# servo.net
KiCad netlist of a schematic drawn in EAGLE
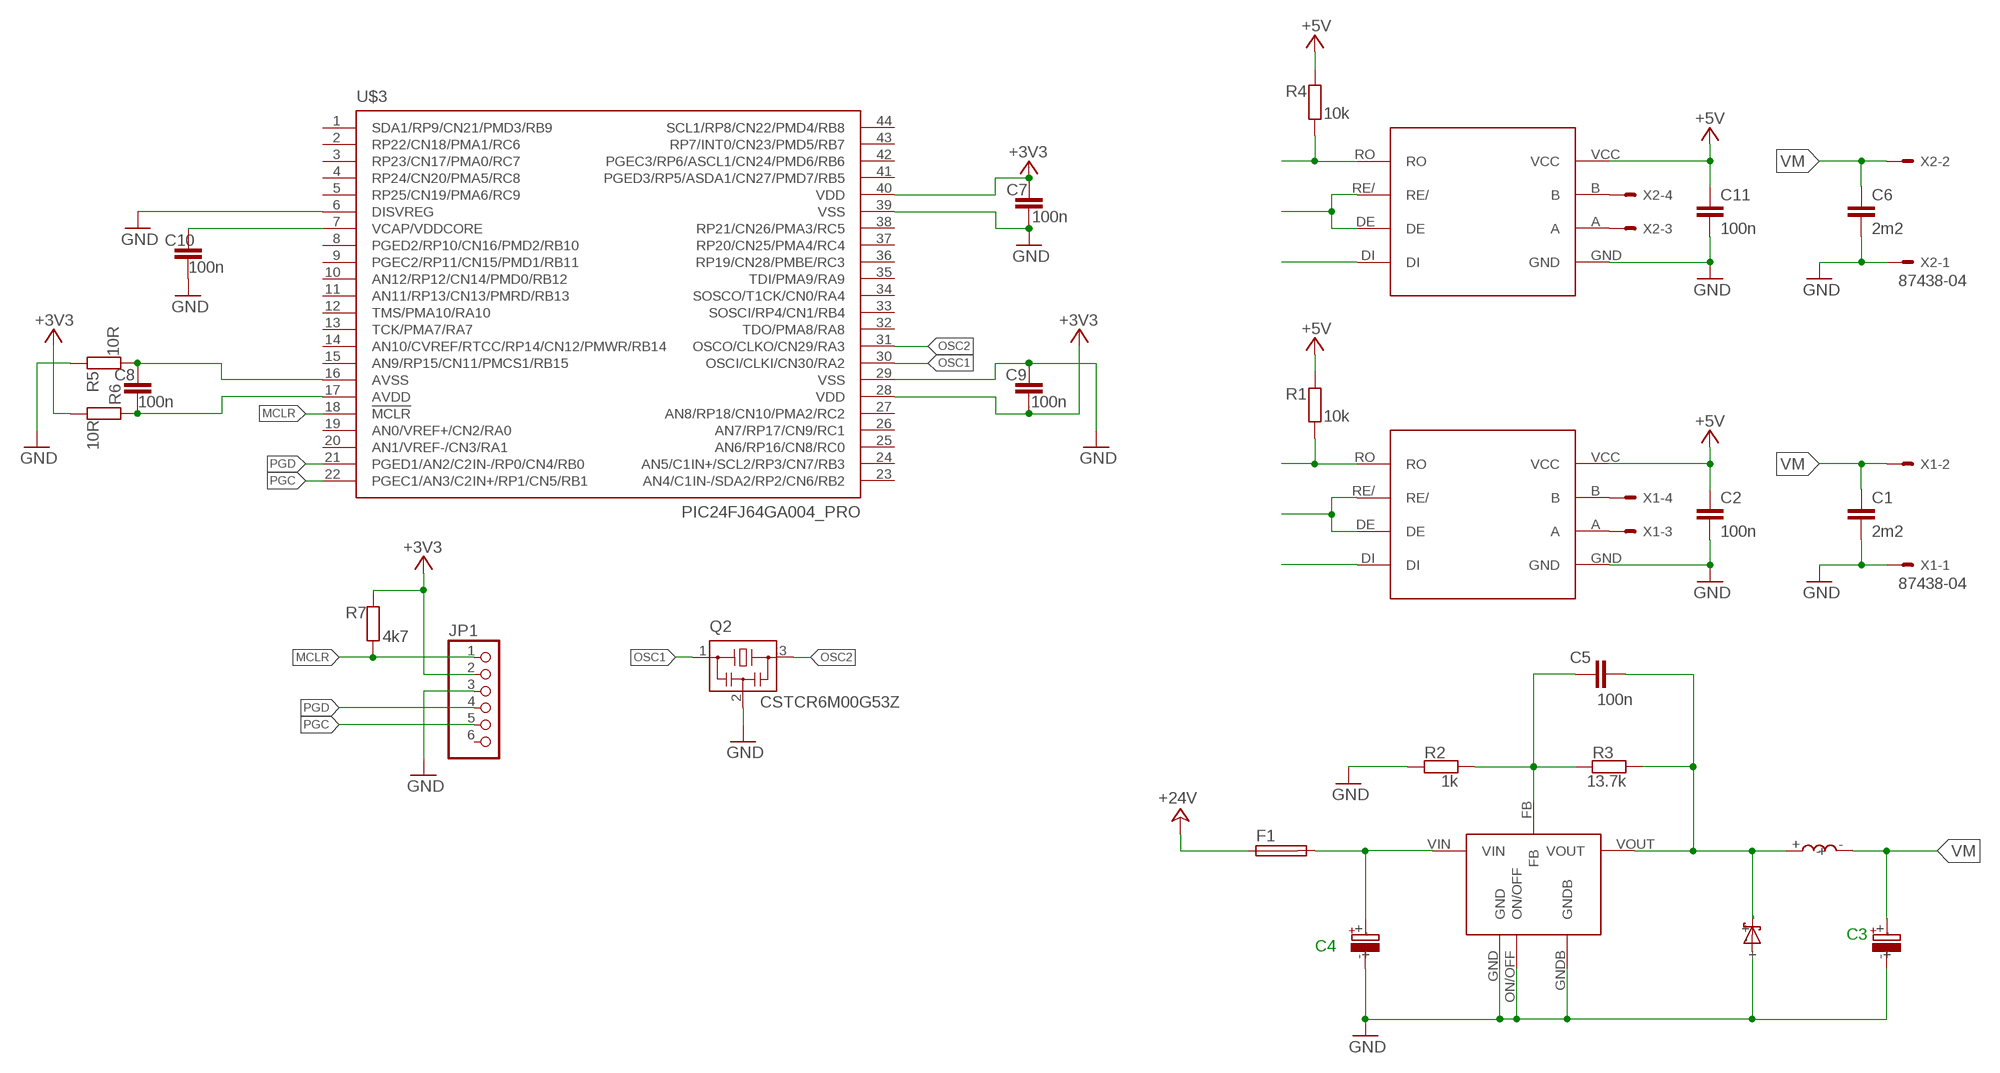
[diagram p0: schematic, sheet 1]

(export (version "E")
  (design (tool "Eeschema 10.0.6"))
  (components
    (comp (ref "C1")
      (value "2m2")
      (footprint "eagle-import:C1206")
      (libsource (lib "eagle-import") (part "resistor_C-EUC1206"))
    )
    (comp (ref "C2")
      (value "100n")
      (footprint "eagle-import:C1206")
      (libsource (lib "eagle-import") (part "resistor_C-EUC1206"))
    )
    (comp (ref "C3")
      (value "220uF")
      (footprint "eagle-import:C220")
      (libsource (lib "eagle-import") (part "C220"))
    )
    (comp (ref "C4")
      (value "680uF")
      (footprint "eagle-import:C680")
      (libsource (lib "eagle-import") (part "C680"))
    )
    (comp (ref "C5")
      (value "100n")
      (footprint "eagle-import:C1206")
      (libsource (lib "eagle-import") (part "resistor_C-EUC1206"))
    )
    (comp (ref "C6")
      (value "2m2")
      (footprint "eagle-import:C1206")
      (libsource (lib "eagle-import") (part "resistor_C-EUC1206"))
    )
    (comp (ref "C7")
      (value "100n")
      (footprint "eagle-import:C1206K")
      (libsource (lib "eagle-import") (part "C-EUC1206K"))
    )
    (comp (ref "C8")
      (value "100n")
      (footprint "eagle-import:C1206K")
      (libsource (lib "eagle-import") (part "C-EUC1206K"))
    )
    (comp (ref "C9")
      (value "100n")
      (footprint "eagle-import:C1206K")
      (libsource (lib "eagle-import") (part "C-EUC1206K"))
    )
    (comp (ref "C10")
      (value "100n")
      (footprint "eagle-import:C1206K")
      (libsource (lib "eagle-import") (part "C-EUC1206K"))
    )
    (comp (ref "C11")
      (value "100n")
      (footprint "eagle-import:C1206")
      (libsource (lib "eagle-import") (part "resistor_C-EUC1206"))
    )
    (comp (ref "F1")
      (value "SH22,5")
      (footprint "eagle-import:SH22,5")
      (fields (field (name "MF") "SCHURTER") (field (name "MPN") "0031.8201"))
      (libsource (lib "eagle-import") (part "SH22,5"))
    )
    (comp (ref "JP1")
      (value "PINHD-1X6")
      (footprint "eagle-import:1X06")
      (libsource (lib "eagle-import") (part "PINHD-1X6"))
    )
    (comp (ref "L1")
      (value "WE-PD")
      (footprint "eagle-import:WE-PD")
      (libsource (lib "eagle-import") (part "WE-PD"))
    )
    (comp (ref "N2")
      (value "MAX485")
      (footprint "eagle-import:SO08")
      (libsource (lib "eagle-import") (part "MAX485"))
    )
    (comp (ref "N3")
      (value "MAX485")
      (footprint "eagle-import:SO08")
      (libsource (lib "eagle-import") (part "MAX485"))
    )
    (comp (ref "Q2")
      (value "CSTCR6M00G53Z")
      (footprint "eagle-import:CSTER12M")
      (fields (field (name "MPN") "CSTCC12M0"))
      (libsource (lib "eagle-import") (part "CSTCR6M00G53Z"))
    )
    (comp (ref "R1")
      (value "10k")
      (footprint "eagle-import:R1206")
      (libsource (lib "eagle-import") (part "resistor_R-EU_R1206"))
    )
    (comp (ref "R2")
      (value "1k")
      (footprint "eagle-import:R1206")
      (libsource (lib "eagle-import") (part "resistor_R-EU_R1206"))
    )
    (comp (ref "R3")
      (value "13.7k")
      (footprint "eagle-import:R1206")
      (libsource (lib "eagle-import") (part "resistor_R-EU_R1206"))
    )
    (comp (ref "R4")
      (value "10k")
      (footprint "eagle-import:R1206")
      (libsource (lib "eagle-import") (part "resistor_R-EU_R1206"))
    )
    (comp (ref "R5")
      (value "10R")
      (footprint "eagle-import:M1206")
      (libsource (lib "eagle-import") (part "R-EU_M1206"))
    )
    (comp (ref "R6")
      (value "10R")
      (footprint "eagle-import:M1206")
      (libsource (lib "eagle-import") (part "R-EU_M1206"))
    )
    (comp (ref "R7")
      (value "4k7")
      (footprint "eagle-import:M1206")
      (libsource (lib "eagle-import") (part "R-EU_M1206"))
    )
    (comp (ref "U$1")
      (value "LM2596")
      (footprint "eagle-import:TO220")
      (libsource (lib "eagle-import") (part "LM2596"))
    )
    (comp (ref "U$2")
      (value "SCHOTTKY")
      (footprint "eagle-import:SCHOTTKY")
      (libsource (lib "eagle-import") (part "SCHOTTKY"))
    )
    (comp (ref "U$3")
      (value "PIC24FJ64GA004_PRO")
      (footprint "eagle-import:TQFP44")
      (libsource (lib "eagle-import") (part "PIC24FJ64GA004_PRO"))
    )
    (comp (ref "X1")
      (value "87438-04")
      (footprint "eagle-import:87438-04")
      (libsource (lib "eagle-import") (part "87438-04"))
    )
    (comp (ref "X2")
      (value "87438-04")
      (footprint "eagle-import:87438-04")
      (libsource (lib "eagle-import") (part "87438-04"))
    )
  )
  (nets
    (net (code "1") (name "+3V3") (class "Default")
      (node (ref "C7") (pin "2") (pinfunction "2_2") (pintype "passive"))
      (node (ref "C9") (pin "2") (pinfunction "2_2") (pintype "passive"))
      (node (ref "JP1") (pin "2") (pinfunction "2_2") (pintype "passive"))
      (node (ref "R6") (pin "2") (pinfunction "2_2") (pintype "passive"))
      (node (ref "R7") (pin "2") (pinfunction "2_2") (pintype "passive"))
      (node (ref "U$3") (pin "28") (pinfunction "VDD_28") (pintype "power_in"))
      (node (ref "U$3") (pin "40") (pinfunction "VDD_40") (pintype "power_in"))
    )
    (net (code "2") (name "+5V") (class "Default")
      (node (ref "C11") (pin "1") (pinfunction "1_1") (pintype "passive"))
      (node (ref "C2") (pin "1") (pinfunction "1_1") (pintype "passive"))
      (node (ref "N2") (pin "VCC") (pinfunction "VCC_VCC") (pintype "bidirectional"))
      (node (ref "N3") (pin "VCC") (pinfunction "VCC_VCC") (pintype "bidirectional"))
      (node (ref "R1") (pin "2") (pinfunction "2_2") (pintype "passive"))
      (node (ref "R4") (pin "2") (pinfunction "2_2") (pintype "passive"))
    )
    (net (code "3") (name "+24V") (class "Default")
      (node (ref "F1") (pin "1") (pinfunction "1_1") (pintype "passive"))
    )
    (net (code "4") (name "GND") (class "Default")
      (node (ref "C1") (pin "2") (pinfunction "2_2") (pintype "passive"))
      (node (ref "C10") (pin "2") (pinfunction "2_2") (pintype "passive"))
      (node (ref "C11") (pin "2") (pinfunction "2_2") (pintype "passive"))
      (node (ref "C2") (pin "2") (pinfunction "2_2") (pintype "passive"))
      (node (ref "C3") (pin "-") (pinfunction "-_-") (pintype "bidirectional"))
      (node (ref "C4") (pin "-") (pinfunction "-_-") (pintype "bidirectional"))
      (node (ref "C6") (pin "2") (pinfunction "2_2") (pintype "passive"))
      (node (ref "C7") (pin "1") (pinfunction "1_1") (pintype "passive"))
      (node (ref "C9") (pin "1") (pinfunction "1_1") (pintype "passive"))
      (node (ref "JP1") (pin "3") (pinfunction "3_3") (pintype "passive"))
      (node (ref "N2") (pin "GND") (pinfunction "GND_GND") (pintype "bidirectional"))
      (node (ref "N3") (pin "GND") (pinfunction "GND_GND") (pintype "bidirectional"))
      (node (ref "Q2") (pin "2") (pinfunction "2_2") (pintype "passive"))
      (node (ref "R2") (pin "2") (pinfunction "2_2") (pintype "passive"))
      (node (ref "R5") (pin "2") (pinfunction "2_2") (pintype "passive"))
      (node (ref "U$1") (pin "GND") (pinfunction "GND_GND") (pintype "bidirectional"))
      (node (ref "U$1") (pin "GNDB") (pinfunction "GNDB_GNDB") (pintype "bidirectional"))
      (node (ref "U$1") (pin "ON/OFF") (pinfunction "ON/OFF_ON/OFF") (pintype "bidirectional"))
      (node (ref "U$2") (pin "-") (pinfunction "-_-") (pintype "bidirectional"))
      (node (ref "U$3") (pin "29") (pinfunction "VSS_29") (pintype "power_in"))
      (node (ref "U$3") (pin "39") (pinfunction "VSS_39") (pintype "power_in"))
      (node (ref "U$3") (pin "6") (pinfunction "DISVREG_6") (pintype "passive"))
      (node (ref "X1") (pin "1") (pinfunction "S_1") (pintype "passive"))
      (node (ref "X2") (pin "1") (pinfunction "S_1") (pintype "passive"))
    )
    (net (code "5") (name "MCLR") (class "Default")
      (node (ref "JP1") (pin "1") (pinfunction "1_1") (pintype "passive"))
      (node (ref "R7") (pin "1") (pinfunction "1_1") (pintype "passive"))
      (node (ref "U$3") (pin "18") (pinfunction "~{MCLR}_18") (pintype "bidirectional"))
    )
    (net (code "6") (name "Net-(C4-Pad+)") (class "Default")
      (node (ref "C4") (pin "+") (pinfunction "+_+") (pintype "bidirectional"))
      (node (ref "F1") (pin "2") (pinfunction "2_2") (pintype "passive"))
      (node (ref "U$1") (pin "VIN") (pinfunction "VIN_VIN") (pintype "bidirectional"))
    )
    (net (code "7") (name "Net-(C5-Pad1)") (class "Default")
      (node (ref "C5") (pin "1") (pinfunction "1_1") (pintype "passive"))
      (node (ref "R2") (pin "1") (pinfunction "1_1") (pintype "passive"))
      (node (ref "R3") (pin "2") (pinfunction "2_2") (pintype "passive"))
      (node (ref "U$1") (pin "FB") (pinfunction "FB_FB") (pintype "bidirectional"))
    )
    (net (code "8") (name "Net-(C5-Pad2)") (class "Default")
      (node (ref "C5") (pin "2") (pinfunction "2_2") (pintype "passive"))
      (node (ref "L1") (pin "+") (pinfunction "+_+") (pintype "bidirectional"))
      (node (ref "R3") (pin "1") (pinfunction "1_1") (pintype "passive"))
      (node (ref "U$1") (pin "VOUT") (pinfunction "VOUT_VOUT") (pintype "bidirectional"))
      (node (ref "U$2") (pin "+") (pinfunction "+_+") (pintype "bidirectional"))
    )
    (net (code "9") (name "Net-(N2-PadDE)") (class "Default")
      (node (ref "N2") (pin "DE") (pinfunction "DE_DE") (pintype "bidirectional"))
      (node (ref "N2") (pin "RE/") (pinfunction "RE/_RE/") (pintype "bidirectional"))
    )
    (net (code "10") (name "Net-(N2-PadRO)") (class "Default")
      (node (ref "N2") (pin "RO") (pinfunction "RO_RO") (pintype "bidirectional"))
      (node (ref "R1") (pin "1") (pinfunction "1_1") (pintype "passive"))
    )
    (net (code "11") (name "Net-(N3-PadDE)") (class "Default")
      (node (ref "N3") (pin "DE") (pinfunction "DE_DE") (pintype "bidirectional"))
      (node (ref "N3") (pin "RE/") (pinfunction "RE/_RE/") (pintype "bidirectional"))
    )
    (net (code "12") (name "Net-(N3-PadRO)") (class "Default")
      (node (ref "N3") (pin "RO") (pinfunction "RO_RO") (pintype "bidirectional"))
      (node (ref "R4") (pin "1") (pinfunction "1_1") (pintype "passive"))
    )
    (net (code "13") (name "Net-(U$3-AVDD)") (class "Default")
      (node (ref "C8") (pin "2") (pinfunction "2_2") (pintype "passive"))
      (node (ref "R6") (pin "1") (pinfunction "1_1") (pintype "passive"))
      (node (ref "U$3") (pin "17") (pinfunction "AVDD_17") (pintype "power_in"))
    )
    (net (code "14") (name "Net-(U$3-AVSS)") (class "Default")
      (node (ref "C8") (pin "1") (pinfunction "1_1") (pintype "passive"))
      (node (ref "R5") (pin "1") (pinfunction "1_1") (pintype "passive"))
      (node (ref "U$3") (pin "16") (pinfunction "AVSS_16") (pintype "power_in"))
    )
    (net (code "15") (name "Net-(U$3-VCAP{slash}VDDCORE)") (class "Default")
      (node (ref "C10") (pin "1") (pinfunction "1_1") (pintype "passive"))
      (node (ref "U$3") (pin "7") (pinfunction "VCAP/VDDCORE_7") (pintype "power_in"))
    )
    (net (code "16") (name "Net-(X1C-S)") (class "Default")
      (node (ref "N2") (pin "A") (pinfunction "A_A") (pintype "bidirectional"))
      (node (ref "X1") (pin "3") (pinfunction "S_3") (pintype "passive"))
    )
    (net (code "17") (name "Net-(X1D-S)") (class "Default")
      (node (ref "N2") (pin "B") (pinfunction "B_B") (pintype "bidirectional"))
      (node (ref "X1") (pin "4") (pinfunction "S_4") (pintype "passive"))
    )
    (net (code "18") (name "Net-(X2C-S)") (class "Default")
      (node (ref "N3") (pin "A") (pinfunction "A_A") (pintype "bidirectional"))
      (node (ref "X2") (pin "3") (pinfunction "S_3") (pintype "passive"))
    )
    (net (code "19") (name "Net-(X2D-S)") (class "Default")
      (node (ref "N3") (pin "B") (pinfunction "B_B") (pintype "bidirectional"))
      (node (ref "X2") (pin "4") (pinfunction "S_4") (pintype "passive"))
    )
    (net (code "20") (name "OSC1") (class "Default")
      (node (ref "Q2") (pin "1") (pinfunction "1_1") (pintype "passive"))
      (node (ref "U$3") (pin "30") (pinfunction "OSCI/CLKI/CN30/RA2_30") (pintype "bidirectional"))
    )
    (net (code "21") (name "OSC2") (class "Default")
      (node (ref "Q2") (pin "3") (pinfunction "3_3") (pintype "passive"))
      (node (ref "U$3") (pin "31") (pinfunction "OSCO/CLKO/CN29/RA3_31") (pintype "bidirectional"))
    )
    (net (code "22") (name "PGC") (class "Default")
      (node (ref "JP1") (pin "5") (pinfunction "5_5") (pintype "passive"))
      (node (ref "U$3") (pin "22") (pinfunction "PGEC1/AN3/C2IN+/RP1/CN5/RB1_22") (pintype "bidirectional"))
    )
    (net (code "23") (name "PGD") (class "Default")
      (node (ref "JP1") (pin "4") (pinfunction "4_4") (pintype "passive"))
      (node (ref "U$3") (pin "21") (pinfunction "PGED1/AN2/C2IN-/RP0/CN4/RB0_21") (pintype "bidirectional"))
    )
    (net (code "24") (name "VM") (class "Default")
      (node (ref "C1") (pin "1") (pinfunction "1_1") (pintype "passive"))
      (node (ref "C3") (pin "+") (pinfunction "+_+") (pintype "bidirectional"))
      (node (ref "C6") (pin "1") (pinfunction "1_1") (pintype "passive"))
      (node (ref "L1") (pin "-") (pinfunction "-_-") (pintype "bidirectional"))
      (node (ref "X1") (pin "2") (pinfunction "S_2") (pintype "passive"))
      (node (ref "X2") (pin "2") (pinfunction "S_2") (pintype "passive"))
    )
    (net (code "25") (name "unconnected-(JP1-Pad6)") (class "Default")
      (node (ref "JP1") (pin "6") (pinfunction "6_6") (pintype "passive"))
    )
    (net (code "26") (name "unconnected-(N2-PadDI)") (class "Default")
      (node (ref "N2") (pin "DI") (pinfunction "DI_DI") (pintype "bidirectional"))
    )
    (net (code "27") (name "unconnected-(N3-PadDI)") (class "Default")
      (node (ref "N3") (pin "DI") (pinfunction "DI_DI") (pintype "bidirectional"))
    )
    (net (code "28") (name "unconnected-(U$3-AN0{slash}VREF+{slash}CN2{slash}RA0-Pad19)") (class "Default")
      (node (ref "U$3") (pin "19") (pinfunction "AN0/VREF+/CN2/RA0_19") (pintype "bidirectional"))
    )
    (net (code "29") (name "unconnected-(U$3-AN1{slash}VREF-{slash}CN3{slash}RA1-Pad20)") (class "Default")
      (node (ref "U$3") (pin "20") (pinfunction "AN1/VREF-/CN3/RA1_20") (pintype "bidirectional"))
    )
    (net (code "30") (name "unconnected-(U$3-AN4{slash}C1IN-{slash}SDA2{slash}RP2{slash}CN6{slash}RB2-Pad23)") (class "Default")
      (node (ref "U$3") (pin "23") (pinfunction "AN4/C1IN-/SDA2/RP2/CN6/RB2_23") (pintype "bidirectional"))
    )
    (net (code "31") (name "unconnected-(U$3-AN5{slash}C1IN+{slash}SCL2{slash}RP3{slash}CN7{slash}RB3-Pad24)") (class "Default")
      (node (ref "U$3") (pin "24") (pinfunction "AN5/C1IN+/SCL2/RP3/CN7/RB3_24") (pintype "bidirectional"))
    )
    (net (code "32") (name "unconnected-(U$3-AN6{slash}RP16{slash}CN8{slash}RC0-Pad25)") (class "Default")
      (node (ref "U$3") (pin "25") (pinfunction "AN6/RP16/CN8/RC0_25") (pintype "bidirectional"))
    )
    (net (code "33") (name "unconnected-(U$3-AN7{slash}RP17{slash}CN9{slash}RC1-Pad26)") (class "Default")
      (node (ref "U$3") (pin "26") (pinfunction "AN7/RP17/CN9/RC1_26") (pintype "bidirectional"))
    )
    (net (code "34") (name "unconnected-(U$3-AN8{slash}RP18{slash}CN10{slash}PMA2{slash}RC2-Pad27)") (class "Default")
      (node (ref "U$3") (pin "27") (pinfunction "AN8/RP18/CN10/PMA2/RC2_27") (pintype "bidirectional"))
    )
    (net (code "35") (name "unconnected-(U$3-AN9{slash}RP15{slash}CN11{slash}PMCS1{slash}RB15-Pad15)") (class "Default")
      (node (ref "U$3") (pin "15") (pinfunction "AN9/RP15/CN11/PMCS1/RB15_15") (pintype "bidirectional"))
    )
    (net (code "36") (name "unconnected-(U$3-AN10{slash}CVREF{slash}RTCC{slash}RP14{slash}CN12{slash}PMWR{slash}RB14-Pad14)") (class "Default")
      (node (ref "U$3") (pin "14") (pinfunction "AN10/CVREF/RTCC/RP14/CN12/PMWR/RB14_14") (pintype "bidirectional"))
    )
    (net (code "37") (name "unconnected-(U$3-AN11{slash}RP13{slash}CN13{slash}PMRD{slash}RB13-Pad11)") (class "Default")
      (node (ref "U$3") (pin "11") (pinfunction "AN11/RP13/CN13/PMRD/RB13_11") (pintype "bidirectional"))
    )
    (net (code "38") (name "unconnected-(U$3-AN12{slash}RP12{slash}CN14{slash}PMD0{slash}RB12-Pad10)") (class "Default")
      (node (ref "U$3") (pin "10") (pinfunction "AN12/RP12/CN14/PMD0/RB12_10") (pintype "bidirectional"))
    )
    (net (code "39") (name "unconnected-(U$3-PGEC2{slash}RP11{slash}CN15{slash}PMD1{slash}RB11-Pad9)") (class "Default")
      (node (ref "U$3") (pin "9") (pinfunction "PGEC2/RP11/CN15/PMD1/RB11_9") (pintype "bidirectional"))
    )
    (net (code "40") (name "unconnected-(U$3-PGEC3{slash}RP6{slash}ASCL1{slash}CN24{slash}PMD6{slash}RB6-Pad42)") (class "Default")
      (node (ref "U$3") (pin "42") (pinfunction "PGEC3/RP6/ASCL1/CN24/PMD6/RB6_42") (pintype "bidirectional"))
    )
    (net (code "41") (name "unconnected-(U$3-PGED2{slash}RP10{slash}CN16{slash}PMD2{slash}RB10-Pad8)") (class "Default")
      (node (ref "U$3") (pin "8") (pinfunction "PGED2/RP10/CN16/PMD2/RB10_8") (pintype "bidirectional"))
    )
    (net (code "42") (name "unconnected-(U$3-PGED3{slash}RP5{slash}ASDA1{slash}CN27{slash}PMD7{slash}RB5-Pad41)") (class "Default")
      (node (ref "U$3") (pin "41") (pinfunction "PGED3/RP5/ASDA1/CN27/PMD7/RB5_41") (pintype "bidirectional"))
    )
    (net (code "43") (name "unconnected-(U$3-RP7{slash}INT0{slash}CN23{slash}PMD5{slash}RB7-Pad43)") (class "Default")
      (node (ref "U$3") (pin "43") (pinfunction "RP7/INT0/CN23/PMD5/RB7_43") (pintype "bidirectional"))
    )
    (net (code "44") (name "unconnected-(U$3-RP19{slash}CN28{slash}PMBE{slash}RC3-Pad36)") (class "Default")
      (node (ref "U$3") (pin "36") (pinfunction "RP19/CN28/PMBE/RC3_36") (pintype "bidirectional"))
    )
    (net (code "45") (name "unconnected-(U$3-RP20{slash}CN25{slash}PMA4{slash}RC4-Pad37)") (class "Default")
      (node (ref "U$3") (pin "37") (pinfunction "RP20/CN25/PMA4/RC4_37") (pintype "bidirectional"))
    )
    (net (code "46") (name "unconnected-(U$3-RP21{slash}CN26{slash}PMA3{slash}RC5-Pad38)") (class "Default")
      (node (ref "U$3") (pin "38") (pinfunction "RP21/CN26/PMA3/RC5_38") (pintype "bidirectional"))
    )
    (net (code "47") (name "unconnected-(U$3-RP22{slash}CN18{slash}PMA1{slash}RC6-Pad2)") (class "Default")
      (node (ref "U$3") (pin "2") (pinfunction "RP22/CN18/PMA1/RC6_2") (pintype "bidirectional"))
    )
    (net (code "48") (name "unconnected-(U$3-RP23{slash}CN17{slash}PMA0{slash}RC7-Pad3)") (class "Default")
      (node (ref "U$3") (pin "3") (pinfunction "RP23/CN17/PMA0/RC7_3") (pintype "bidirectional"))
    )
    (net (code "49") (name "unconnected-(U$3-RP24{slash}CN20{slash}PMA5{slash}RC8-Pad4)") (class "Default")
      (node (ref "U$3") (pin "4") (pinfunction "RP24/CN20/PMA5/RC8_4") (pintype "bidirectional"))
    )
    (net (code "50") (name "unconnected-(U$3-RP25{slash}CN19{slash}PMA6{slash}RC9-Pad5)") (class "Default")
      (node (ref "U$3") (pin "5") (pinfunction "RP25/CN19/PMA6/RC9_5") (pintype "bidirectional"))
    )
    (net (code "51") (name "unconnected-(U$3-SCL1{slash}RP8{slash}CN22{slash}PMD4{slash}RB8-Pad44)") (class "Default")
      (node (ref "U$3") (pin "44") (pinfunction "SCL1/RP8/CN22/PMD4/RB8_44") (pintype "bidirectional"))
    )
    (net (code "52") (name "unconnected-(U$3-SDA1{slash}RP9{slash}CN21{slash}PMD3{slash}RB9-Pad1)") (class "Default")
      (node (ref "U$3") (pin "1") (pinfunction "SDA1/RP9/CN21/PMD3/RB9_1") (pintype "bidirectional"))
    )
    (net (code "53") (name "unconnected-(U$3-SOSCI{slash}RP4{slash}CN1{slash}RB4-Pad33)") (class "Default")
      (node (ref "U$3") (pin "33") (pinfunction "SOSCI/RP4/CN1/RB4_33") (pintype "bidirectional"))
    )
    (net (code "54") (name "unconnected-(U$3-SOSCO{slash}T1CK{slash}CN0{slash}RA4-Pad34)") (class "Default")
      (node (ref "U$3") (pin "34") (pinfunction "SOSCO/T1CK/CN0/RA4_34") (pintype "bidirectional"))
    )
    (net (code "55") (name "unconnected-(U$3-TCK{slash}PMA7{slash}RA7-Pad13)") (class "Default")
      (node (ref "U$3") (pin "13") (pinfunction "TCK/PMA7/RA7_13") (pintype "input"))
    )
    (net (code "56") (name "unconnected-(U$3-TDI{slash}PMA9{slash}RA9-Pad35)") (class "Default")
      (node (ref "U$3") (pin "35") (pinfunction "TDI/PMA9/RA9_35") (pintype "input"))
    )
    (net (code "57") (name "unconnected-(U$3-TDO{slash}PMA8{slash}RA8-Pad32)") (class "Default")
      (node (ref "U$3") (pin "32") (pinfunction "TDO/PMA8/RA8_32") (pintype "output"))
    )
    (net (code "58") (name "unconnected-(U$3-TMS{slash}PMA10{slash}RA10-Pad12)") (class "Default")
      (node (ref "U$3") (pin "12") (pinfunction "TMS/PMA10/RA10_12") (pintype "input"))
    )
  )
)
